# Input_Analog.net
KiCad netlist of a schematic drawn in Altium Designer
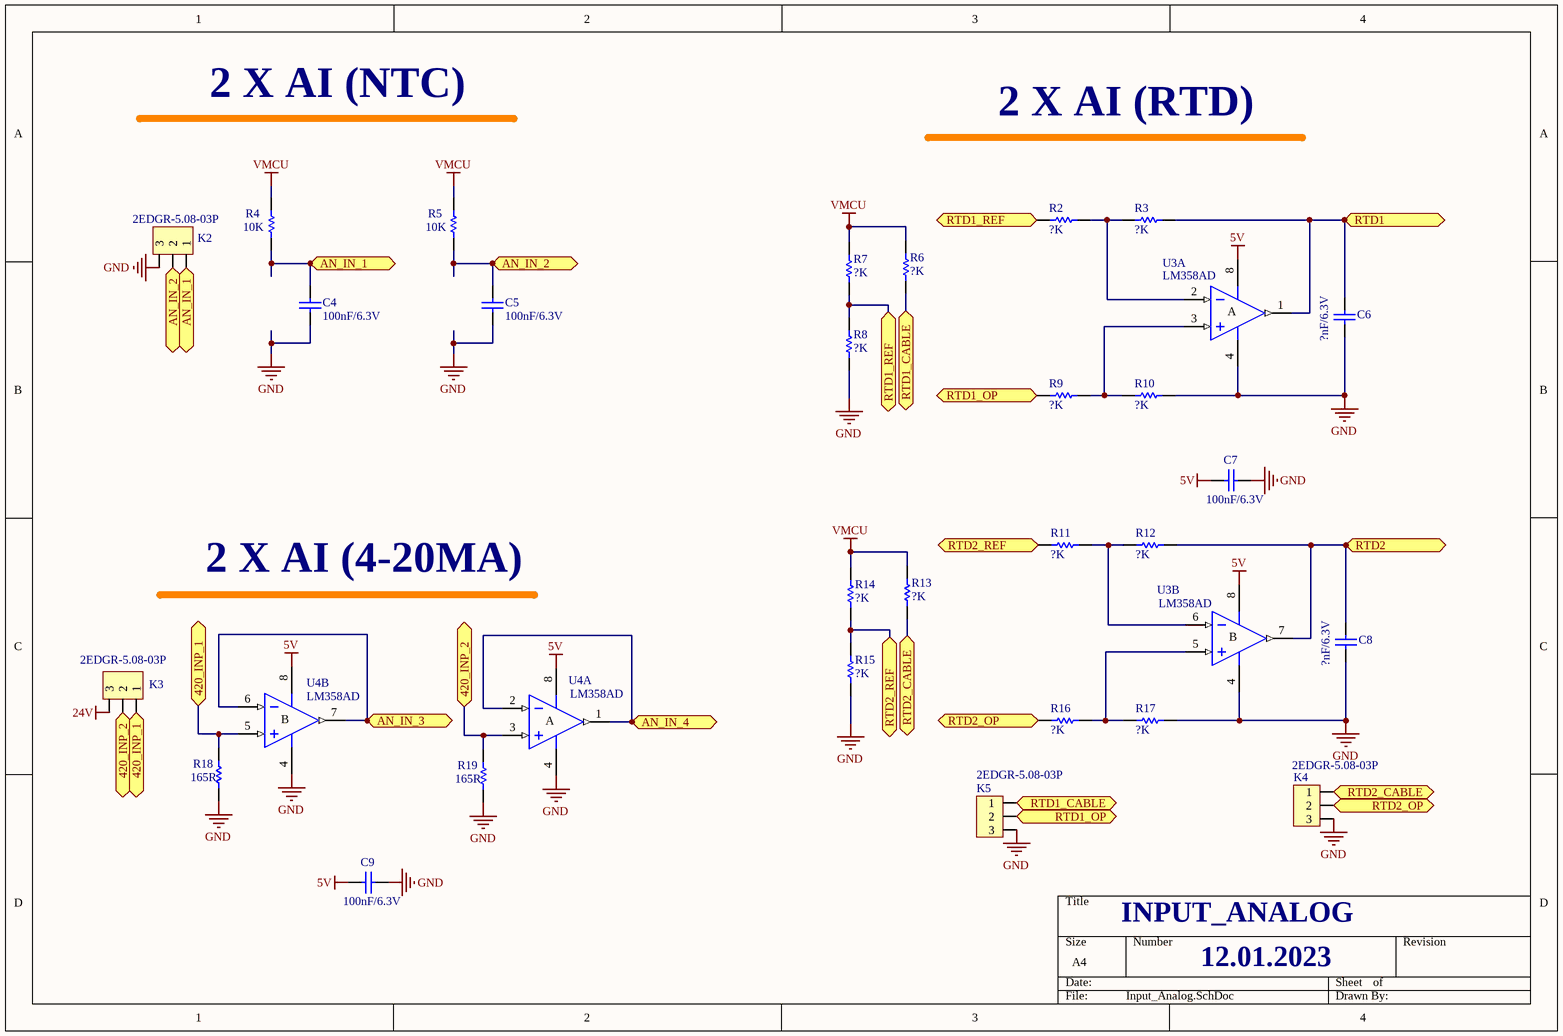
[diagram p0: Input_Analog.SchDoc]

(export (version "E")
  (design (tool "Eeschema 10.0.6"))
  (components
    (comp (ref "C4")
      (value "100nF/6.3V")
      (footprint "CAP0603W")
      (description "CAPACITOR 0603 Case")
      (fields (field (name "PUBLISHER") "Altium Limited"))
      (libsource (lib "geolib") (part "CAP1"))
    )
    (comp (ref "C5")
      (value "100nF/6.3V")
      (footprint "CAP0603W")
      (description "CAPACITOR 0603 Case")
      (fields (field (name "PUBLISHER") "Altium Limited"))
      (libsource (lib "geolib") (part "CAP1"))
    )
    (comp (ref "C6")
      (value "?nF/6.3V")
      (footprint "CAP0603W")
      (description "CAPACITOR 0603 Case")
      (fields (field (name "PUBLISHER") "Altium Limited"))
      (libsource (lib "geolib") (part "CAP1"))
    )
    (comp (ref "C7")
      (value "100nF/6.3V")
      (footprint "CAP0603W")
      (description "CAPACITOR 0603 Case")
      (fields (field (name "PUBLISHER") "Altium Limited"))
      (libsource (lib "geolib") (part "CAP1"))
    )
    (comp (ref "C8")
      (value "?nF/6.3V")
      (footprint "CAP0603W")
      (description "CAPACITOR 0603 Case")
      (fields (field (name "PUBLISHER") "Altium Limited"))
      (libsource (lib "geolib") (part "CAP1"))
    )
    (comp (ref "C9")
      (value "100nF/6.3V")
      (footprint "CAP0603W")
      (description "CAPACITOR 0603 Case")
      (fields (field (name "PUBLISHER") "Altium Limited"))
      (libsource (lib "geolib") (part "CAP1"))
    )
    (comp (ref "K2")
      (value "2EDGR-5.08-03P")
      (footprint "CON_DG129_03P")
      (description "CONNECTOR 5.08mm 3PIN 90DEG")
      (libsource (lib "geolib") (part "KLEMENS_3P"))
    )
    (comp (ref "K3")
      (value "2EDGR-5.08-03P")
      (footprint "CON_DG129_03P")
      (description "CONNECTOR 5.08mm 3PIN 90DEG")
      (libsource (lib "geolib") (part "KLEMENS_3P"))
    )
    (comp (ref "K4")
      (value "2EDGR-5.08-03P")
      (footprint "CON_DG129_03P")
      (description "CONNECTOR 5.08mm 3PIN 90DEG")
      (libsource (lib "") (part "KLEMENS_3P_1"))
    )
    (comp (ref "K5")
      (value "2EDGR-5.08-03P")
      (footprint "CON_DG129_03P")
      (description "CONNECTOR 5.08mm 3PIN 90DEG")
      (libsource (lib "") (part "KLEMENS_3P_1"))
    )
    (comp (ref "R2")
      (value "?K")
      (footprint "RES1608[0603]")
      (description "RESISTOR 0603 Case %1")
      (fields (field (name "PUBLISHER") "Altium Limited"))
      (libsource (lib "geolib") (part "RES"))
    )
    (comp (ref "R3")
      (value "?K")
      (footprint "RES1608[0603]")
      (description "RESISTOR 0603 Case %1")
      (fields (field (name "PUBLISHER") "Altium Limited"))
      (libsource (lib "geolib") (part "RES"))
    )
    (comp (ref "R4")
      (value "10K")
      (footprint "RES1608[0603]")
      (description "RESISTOR 0603 Case %1")
      (fields (field (name "PUBLISHER") "Altium Limited"))
      (libsource (lib "geolib") (part "RES"))
    )
    (comp (ref "R5")
      (value "10K")
      (footprint "RES1608[0603]")
      (description "RESISTOR 0603 Case %1")
      (fields (field (name "PUBLISHER") "Altium Limited"))
      (libsource (lib "geolib") (part "RES"))
    )
    (comp (ref "R6")
      (value "?K")
      (footprint "RES1608[0603]")
      (description "RESISTOR 0603 Case %1")
      (fields (field (name "PUBLISHER") "Altium Limited"))
      (libsource (lib "geolib") (part "RES"))
    )
    (comp (ref "R7")
      (value "?K")
      (footprint "RES1608[0603]")
      (description "RESISTOR 0603 Case %1")
      (fields (field (name "PUBLISHER") "Altium Limited"))
      (libsource (lib "geolib") (part "RES"))
    )
    (comp (ref "R8")
      (value "?K")
      (footprint "RES1608[0603]")
      (description "RESISTOR 0603 Case %1")
      (fields (field (name "PUBLISHER") "Altium Limited"))
      (libsource (lib "geolib") (part "RES"))
    )
    (comp (ref "R9")
      (value "?K")
      (footprint "RES1608[0603]")
      (description "RESISTOR 0603 Case %1")
      (fields (field (name "PUBLISHER") "Altium Limited"))
      (libsource (lib "geolib") (part "RES"))
    )
    (comp (ref "R10")
      (value "?K")
      (footprint "RES1608[0603]")
      (description "RESISTOR 0603 Case %1")
      (fields (field (name "PUBLISHER") "Altium Limited"))
      (libsource (lib "geolib") (part "RES"))
    )
    (comp (ref "R11")
      (value "?K")
      (footprint "RES1608[0603]")
      (description "RESISTOR 0603 Case %1")
      (fields (field (name "PUBLISHER") "Altium Limited"))
      (libsource (lib "geolib") (part "RES"))
    )
    (comp (ref "R12")
      (value "?K")
      (footprint "RES1608[0603]")
      (description "RESISTOR 0603 Case %1")
      (fields (field (name "PUBLISHER") "Altium Limited"))
      (libsource (lib "geolib") (part "RES"))
    )
    (comp (ref "R13")
      (value "?K")
      (footprint "RES1608[0603]")
      (description "RESISTOR 0603 Case %1")
      (fields (field (name "PUBLISHER") "Altium Limited"))
      (libsource (lib "geolib") (part "RES"))
    )
    (comp (ref "R14")
      (value "?K")
      (footprint "RES1608[0603]")
      (description "RESISTOR 0603 Case %1")
      (fields (field (name "PUBLISHER") "Altium Limited"))
      (libsource (lib "geolib") (part "RES"))
    )
    (comp (ref "R15")
      (value "?K")
      (footprint "RES1608[0603]")
      (description "RESISTOR 0603 Case %1")
      (fields (field (name "PUBLISHER") "Altium Limited"))
      (libsource (lib "geolib") (part "RES"))
    )
    (comp (ref "R16")
      (value "?K")
      (footprint "RES1608[0603]")
      (description "RESISTOR 0603 Case %1")
      (fields (field (name "PUBLISHER") "Altium Limited"))
      (libsource (lib "geolib") (part "RES"))
    )
    (comp (ref "R17")
      (value "?K")
      (footprint "RES1608[0603]")
      (description "RESISTOR 0603 Case %1")
      (fields (field (name "PUBLISHER") "Altium Limited"))
      (libsource (lib "geolib") (part "RES"))
    )
    (comp (ref "R18")
      (value "165R")
      (footprint "RES1608[0603]")
      (description "RESISTOR 0603 Case %1")
      (fields (field (name "PUBLISHER") "Altium Limited"))
      (libsource (lib "geolib") (part "RES"))
    )
    (comp (ref "R19")
      (value "165R")
      (footprint "RES1608[0603]")
      (description "RESISTOR 0603 Case %1")
      (fields (field (name "PUBLISHER") "Altium Limited"))
      (libsource (lib "geolib") (part "RES"))
    )
    (comp (ref "U3")
      (value "LM358AD")
      (footprint "SO8")
      (description "OPAMP Low-Power Dual Operational Amplifier")
      (fields (field (name "PUBLISHER") "Altium Limited"))
      (libsource (lib "geolib") (part "LM358AD"))
    )
    (comp (ref "U4")
      (value "LM358AD")
      (footprint "SO8")
      (description "Low-Power Dual Operational Amplifier")
      (fields (field (name "PUBLISHER") "Altium Limited"))
      (libsource (lib "geolib") (part "LM358AD"))
    )
  )
  (nets
    (net (code "1") (name "/420_INP_1") (class "Default")
      (node (ref "K3") (pin "1") (pinfunction "1_1") (pintype "passive"))
      (node (ref "R18") (pin "1") (pinfunction "1_1") (pintype "passive"))
      (node (ref "U4") (pin "5") (pinfunction "IN+_5") (pintype "input"))
    )
    (net (code "2") (name "/420_INP_2") (class "Default")
      (node (ref "K3") (pin "2") (pinfunction "2_2") (pintype "passive"))
      (node (ref "R19") (pin "1") (pinfunction "1_1") (pintype "passive"))
      (node (ref "U4") (pin "3") (pinfunction "IN+_3") (pintype "input"))
    )
    (net (code "3") (name "/AN_IN_1") (class "Default")
      (node (ref "C4") (pin "1") (pinfunction "1_1") (pintype "passive"))
      (node (ref "K2") (pin "1") (pinfunction "1_1") (pintype "passive"))
      (node (ref "R4") (pin "2") (pinfunction "2_2") (pintype "passive"))
    )
    (net (code "4") (name "/AN_IN_2") (class "Default")
      (node (ref "C5") (pin "1") (pinfunction "1_1") (pintype "passive"))
      (node (ref "K2") (pin "2") (pinfunction "2_2") (pintype "passive"))
      (node (ref "R5") (pin "2") (pinfunction "2_2") (pintype "passive"))
    )
    (net (code "5") (name "/AN_IN_3") (class "Default")
      (node (ref "U4") (pin "6") (pinfunction "IN-_6") (pintype "input"))
      (node (ref "U4") (pin "7") (pinfunction "OUT_7") (pintype "output"))
    )
    (net (code "6") (name "/AN_IN_4") (class "Default")
      (node (ref "U4") (pin "1") (pinfunction "OUT_1") (pintype "output"))
      (node (ref "U4") (pin "2") (pinfunction "IN-_2") (pintype "input"))
    )
    (net (code "7") (name "/RTD1") (class "Default")
      (node (ref "C6") (pin "1") (pinfunction "1_1") (pintype "passive"))
      (node (ref "R3") (pin "1") (pinfunction "1_1") (pintype "passive"))
      (node (ref "U3") (pin "1") (pinfunction "OUT_1") (pintype "output"))
    )
    (net (code "8") (name "/RTD1_CABLE") (class "Default")
      (node (ref "K5") (pin "1") (pinfunction "1_1") (pintype "passive"))
      (node (ref "R6") (pin "1") (pinfunction "1_1") (pintype "passive"))
    )
    (net (code "9") (name "/RTD1_OP") (class "Default")
      (node (ref "K5") (pin "2") (pinfunction "2_2") (pintype "passive"))
      (node (ref "R9") (pin "2") (pinfunction "2_2") (pintype "passive"))
    )
    (net (code "10") (name "/RTD1_REF") (class "Default")
      (node (ref "R2") (pin "2") (pinfunction "2_2") (pintype "passive"))
      (node (ref "R7") (pin "1") (pinfunction "1_1") (pintype "passive"))
      (node (ref "R8") (pin "2") (pinfunction "2_2") (pintype "passive"))
    )
    (net (code "11") (name "/RTD2") (class "Default")
      (node (ref "C8") (pin "1") (pinfunction "1_1") (pintype "passive"))
      (node (ref "R12") (pin "1") (pinfunction "1_1") (pintype "passive"))
      (node (ref "U3") (pin "7") (pinfunction "OUT_7") (pintype "output"))
    )
    (net (code "12") (name "/RTD2_CABLE") (class "Default")
      (node (ref "K4") (pin "1") (pinfunction "1_1") (pintype "passive"))
      (node (ref "R13") (pin "1") (pinfunction "1_1") (pintype "passive"))
    )
    (net (code "13") (name "/RTD2_OP") (class "Default")
      (node (ref "K4") (pin "2") (pinfunction "2_2") (pintype "passive"))
      (node (ref "R16") (pin "2") (pinfunction "2_2") (pintype "passive"))
    )
    (net (code "14") (name "/RTD2_REF") (class "Default")
      (node (ref "R11") (pin "2") (pinfunction "2_2") (pintype "passive"))
      (node (ref "R14") (pin "1") (pinfunction "1_1") (pintype "passive"))
      (node (ref "R15") (pin "2") (pinfunction "2_2") (pintype "passive"))
    )
    (net (code "15") (name "5V") (class "Default")
      (node (ref "C7") (pin "1") (pinfunction "1_1") (pintype "passive"))
      (node (ref "C9") (pin "1") (pinfunction "1_1") (pintype "passive"))
      (node (ref "U3") (pin "8") (pinfunction "V+_8") (pintype "power_in"))
      (node (ref "U4") (pin "8") (pinfunction "V+_8") (pintype "power_in"))
    )
    (net (code "16") (name "24V") (class "Default")
      (node (ref "K3") (pin "3") (pinfunction "3_3") (pintype "passive"))
    )
    (net (code "17") (name "GND") (class "Default")
      (node (ref "C4") (pin "2") (pinfunction "2_2") (pintype "passive"))
      (node (ref "C5") (pin "2") (pinfunction "2_2") (pintype "passive"))
      (node (ref "C6") (pin "2") (pinfunction "2_2") (pintype "passive"))
      (node (ref "C7") (pin "2") (pinfunction "2_2") (pintype "passive"))
      (node (ref "C8") (pin "2") (pinfunction "2_2") (pintype "passive"))
      (node (ref "C9") (pin "2") (pinfunction "2_2") (pintype "passive"))
      (node (ref "K2") (pin "3") (pinfunction "3_3") (pintype "passive"))
      (node (ref "K4") (pin "3") (pinfunction "3_3") (pintype "passive"))
      (node (ref "K5") (pin "3") (pinfunction "3_3") (pintype "passive"))
      (node (ref "R10") (pin "1") (pinfunction "1_1") (pintype "passive"))
      (node (ref "R15") (pin "1") (pinfunction "1_1") (pintype "passive"))
      (node (ref "R17") (pin "1") (pinfunction "1_1") (pintype "passive"))
      (node (ref "R18") (pin "2") (pinfunction "2_2") (pintype "passive"))
      (node (ref "R19") (pin "2") (pinfunction "2_2") (pintype "passive"))
      (node (ref "R8") (pin "1") (pinfunction "1_1") (pintype "passive"))
      (node (ref "U3") (pin "4") (pinfunction "V-_4") (pintype "power_in"))
      (node (ref "U4") (pin "4") (pinfunction "V-_4") (pintype "power_in"))
    )
    (net (code "18") (name "Net-(U3A-IN+)") (class "Default")
      (node (ref "R10") (pin "2") (pinfunction "2_2") (pintype "passive"))
      (node (ref "R9") (pin "1") (pinfunction "1_1") (pintype "passive"))
      (node (ref "U3") (pin "3") (pinfunction "IN+_3") (pintype "input"))
    )
    (net (code "19") (name "Net-(U3A-IN-)") (class "Default")
      (node (ref "R2") (pin "1") (pinfunction "1_1") (pintype "passive"))
      (node (ref "R3") (pin "2") (pinfunction "2_2") (pintype "passive"))
      (node (ref "U3") (pin "2") (pinfunction "IN-_2") (pintype "input"))
    )
    (net (code "20") (name "Net-(U3B-IN+)") (class "Default")
      (node (ref "R16") (pin "1") (pinfunction "1_1") (pintype "passive"))
      (node (ref "R17") (pin "2") (pinfunction "2_2") (pintype "passive"))
      (node (ref "U3") (pin "5") (pinfunction "IN+_5") (pintype "input"))
    )
    (net (code "21") (name "Net-(U3B-IN-)") (class "Default")
      (node (ref "R11") (pin "1") (pinfunction "1_1") (pintype "passive"))
      (node (ref "R12") (pin "2") (pinfunction "2_2") (pintype "passive"))
      (node (ref "U3") (pin "6") (pinfunction "IN-_6") (pintype "input"))
    )
    (net (code "22") (name "VMCU") (class "Default")
      (node (ref "R13") (pin "2") (pinfunction "2_2") (pintype "passive"))
      (node (ref "R14") (pin "2") (pinfunction "2_2") (pintype "passive"))
      (node (ref "R4") (pin "1") (pinfunction "1_1") (pintype "passive"))
      (node (ref "R5") (pin "1") (pinfunction "1_1") (pintype "passive"))
      (node (ref "R6") (pin "2") (pinfunction "2_2") (pintype "passive"))
      (node (ref "R7") (pin "2") (pinfunction "2_2") (pintype "passive"))
    )
  )
)
